# IoTaWat_DIN.net
KiCad netlist of a schematic drawn in Altium Designer
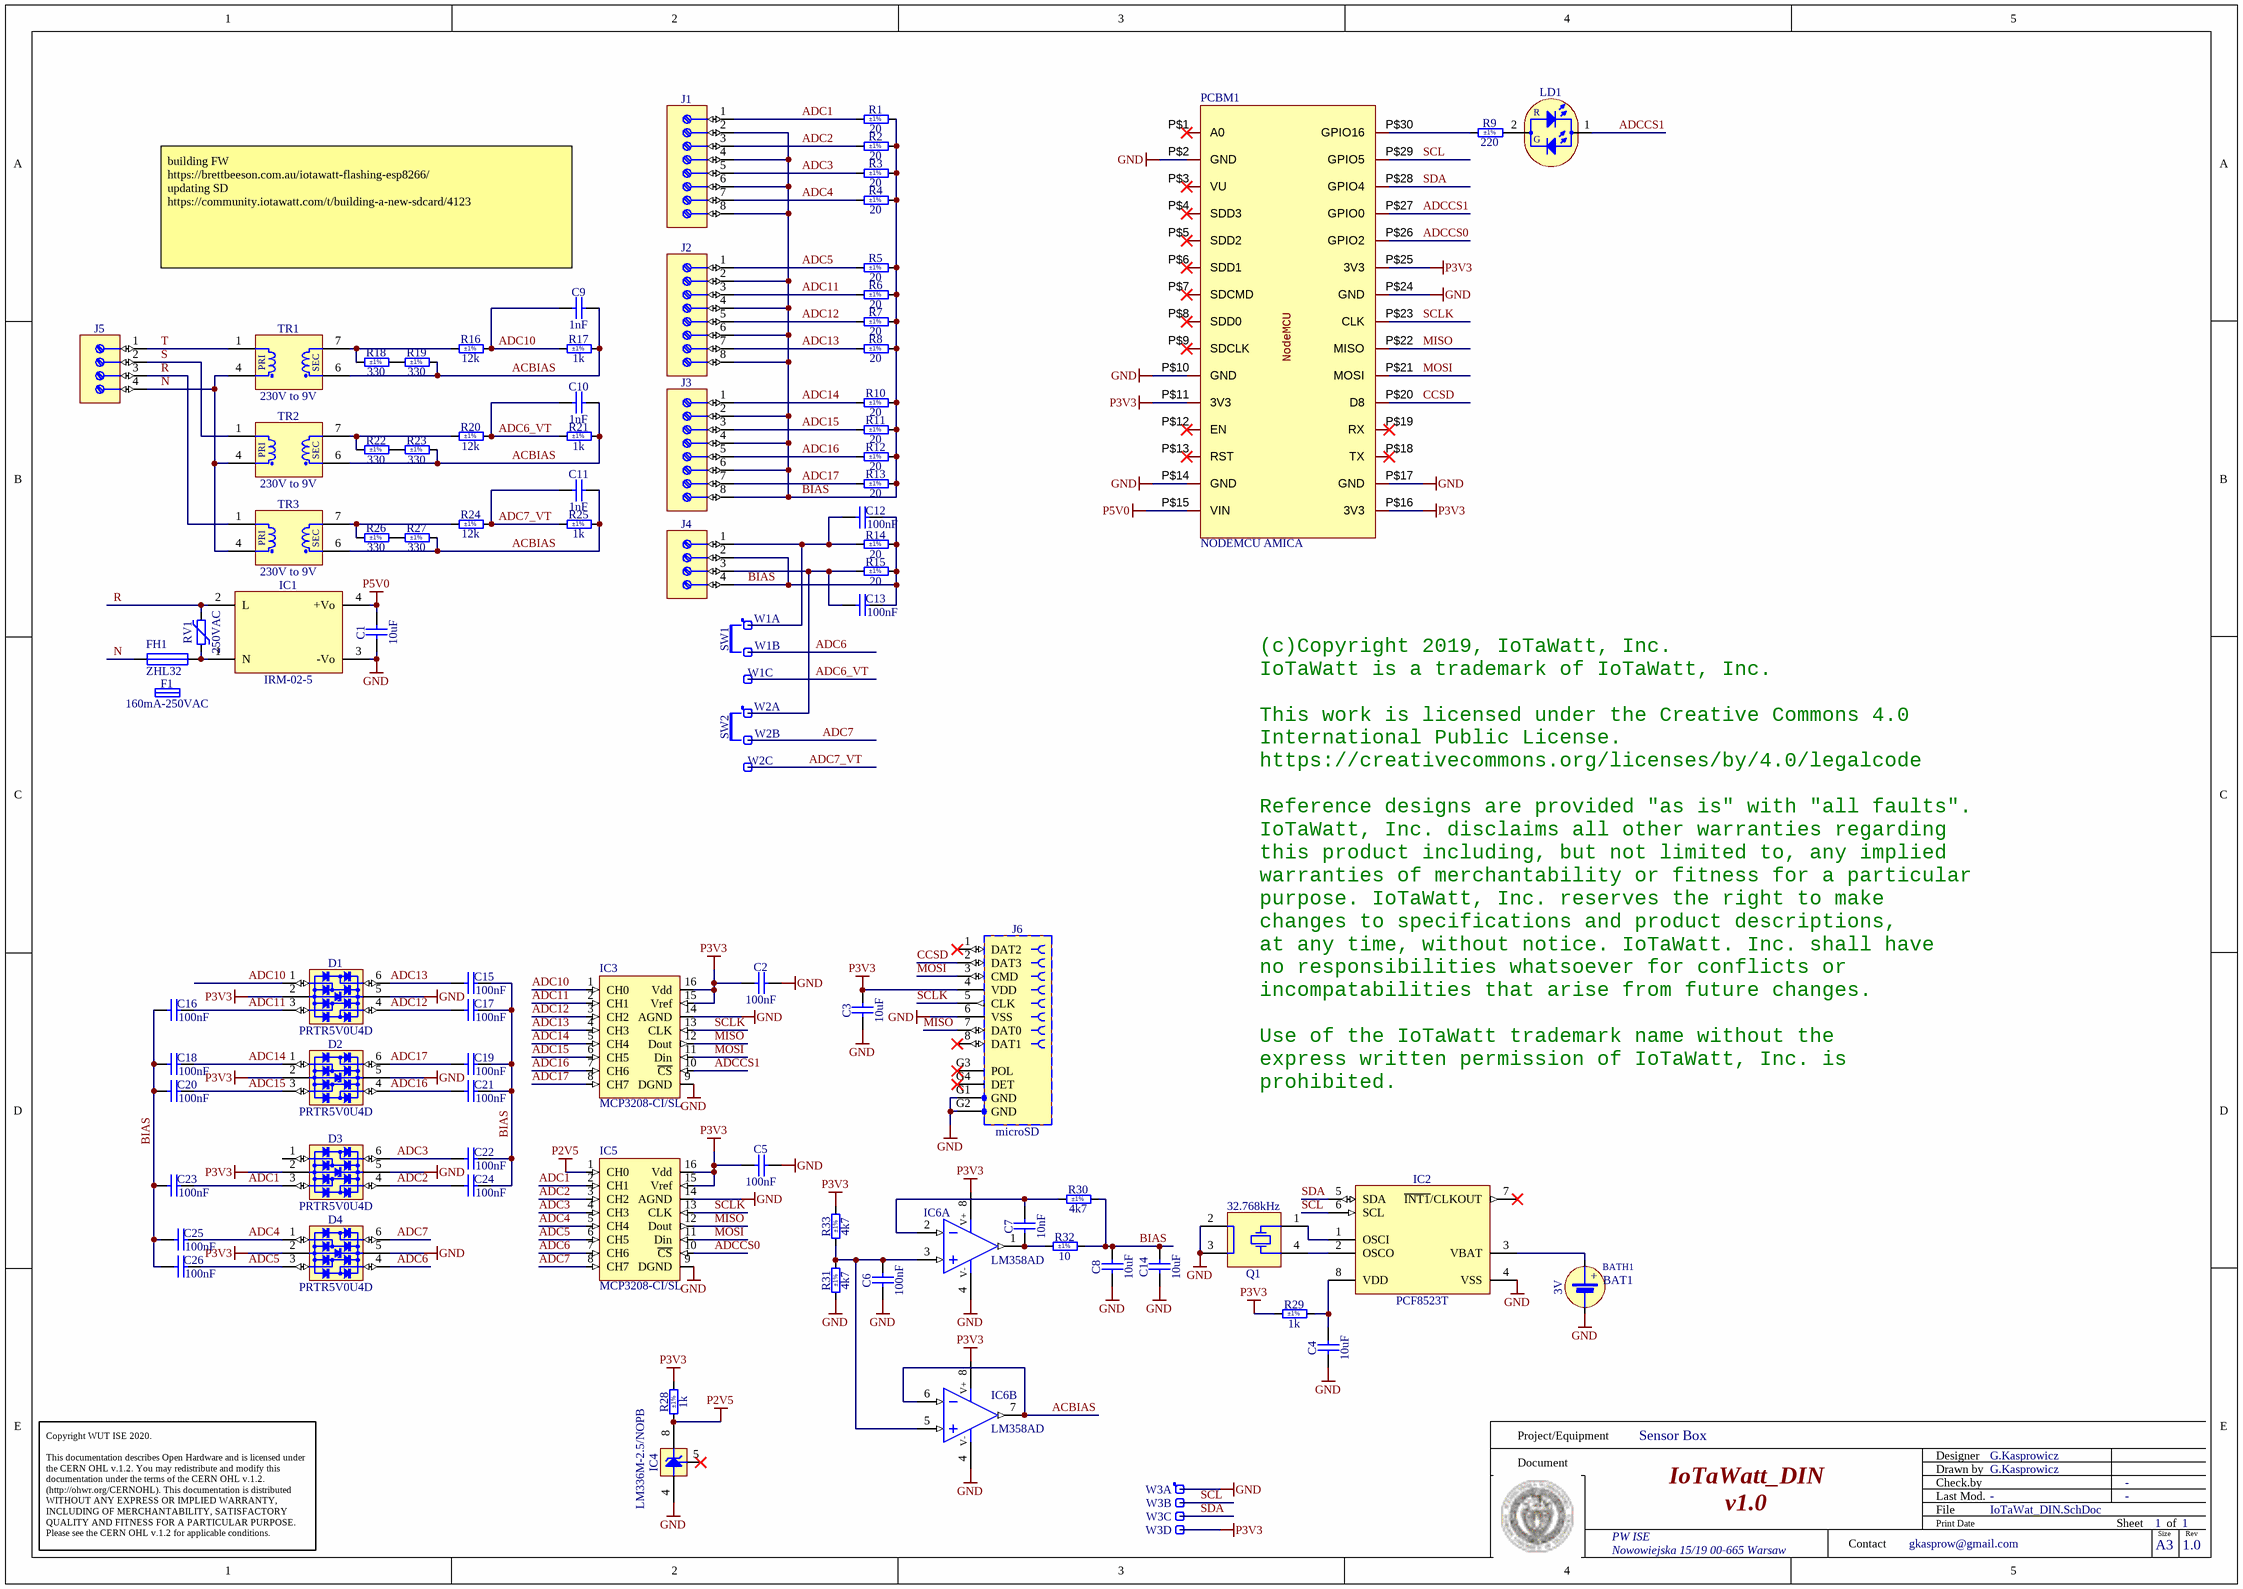
[diagram p0: IoTaWat_DIN.SchDoc]

(export (version "E")
  (design (tool "Eeschema 10.0.6"))
  (components
    (comp (ref "BAT1")
      (value "3V")
      (footprint "BAT_VARTA_CR1220")
      (description "Battery for use only with Socket Holder")
      (fields
        (field (name "PART NUMBER") "BAT_VARTA_CR1220")
        (field (name "POWER") "35mAh")
        (field (name "AUTHOR") "CERN DEM JLC")
      )
      (libsource (lib "Eletro-mechanical") (part "Battery No Pin"))
    )
    (comp (ref "BATH1")
      (value "~")
      (footprint "BATH_KEYSTONE_3000")
      (description "Battery Holder whit 2 Pin")
      (fields
        (field (name "PART NUMBER") "BATH_KEYSTONE_3000")
        (field (name "MANUFACTURER") "KEYSTONE")
        (field (name "AUTHOR") "CERN DEM JLC")
      )
      (libsource (lib "Eletro-mechanical") (part "Battery Holder 2 Pin"))
    )
    (comp (ref "C1")
      (value "10uF")
      (footprint "CAPC2012X135N")
      (description "Non-polarised capacitor")
      (fields
        (field (name "PART NUMBER") "CC0805_10UF_10V_10%_X7R")
        (field (name "VOLTAGE") "10V")
        (field (name "AUTHOR") "CERN DEM JLC")
      )
      (libsource (lib "Capacitors") (part "Capacitor - non polarized"))
    )
    (comp (ref "C2")
      (value "100nF")
      (footprint "CAPC1608X87N")
      (description "Non-polarised capacitor")
      (fields
        (field (name "PART NUMBER") "CC0603_100NF_50V_10%_X5R")
        (field (name "VOLTAGE") "50V")
        (field (name "AUTHOR") "CERN DEM MR")
      )
      (libsource (lib "Capacitors") (part "Capacitor - non polarized"))
    )
    (comp (ref "C3")
      (value "10uF")
      (footprint "CAPC2012X135N")
      (description "Non-polarised capacitor")
      (fields
        (field (name "PART NUMBER") "CC0805_10UF_10V_10%_X7R")
        (field (name "VOLTAGE") "10V")
        (field (name "AUTHOR") "CERN DEM JLC")
      )
      (libsource (lib "Capacitors") (part "Capacitor - non polarized"))
    )
    (comp (ref "C4")
      (value "10uF")
      (footprint "CAPC2012X135N")
      (description "Non-polarised capacitor")
      (fields
        (field (name "PART NUMBER") "CC0805_10UF_10V_10%_X7R")
        (field (name "VOLTAGE") "10V")
        (field (name "AUTHOR") "CERN DEM JLC")
      )
      (libsource (lib "Capacitors") (part "Capacitor - non polarized"))
    )
    (comp (ref "C5")
      (value "100nF")
      (footprint "CAPC1608X87N")
      (description "Non-polarised capacitor")
      (fields
        (field (name "PART NUMBER") "CC0603_100NF_50V_10%_X5R")
        (field (name "VOLTAGE") "50V")
        (field (name "AUTHOR") "CERN DEM MR")
      )
      (libsource (lib "Capacitors") (part "Capacitor - non polarized"))
    )
    (comp (ref "C6")
      (value "100nF")
      (footprint "CAPC1608X87N")
      (description "Non-polarised capacitor")
      (fields
        (field (name "PART NUMBER") "CC0603_100NF_50V_10%_X5R")
        (field (name "VOLTAGE") "50V")
        (field (name "AUTHOR") "CERN DEM MR")
      )
      (libsource (lib "Capacitors") (part "Capacitor - non polarized"))
    )
    (comp (ref "C7")
      (value "10nF")
      (footprint "CAPC1608X87N")
      (description "Non-polarised capacitor")
      (fields
        (field (name "PART NUMBER") "CC0603_10NF_50V_5%_C0G")
        (field (name "VOLTAGE") "50V")
        (field (name "AUTHOR") "CERN DEM JLC")
      )
      (libsource (lib "Capacitors") (part "Capacitor - non polarized"))
    )
    (comp (ref "C8")
      (value "10uF")
      (footprint "CAPC2012X135N")
      (description "Non-polarised capacitor")
      (fields
        (field (name "PART NUMBER") "CC0805_10UF_10V_10%_X7R")
        (field (name "VOLTAGE") "10V")
        (field (name "AUTHOR") "CERN DEM JLC")
      )
      (libsource (lib "Capacitors") (part "Capacitor - non polarized"))
    )
    (comp (ref "C9")
      (value "1nF")
      (footprint "CAPC1608X90N")
      (description "Non-polarised capacitor")
      (fields
        (field (name "PART NUMBER") "CC0603_1NF_50V_1%_NP0")
        (field (name "VOLTAGE") "50V")
        (field (name "AUTHOR") "CERN DEM JLC")
      )
      (libsource (lib "Capacitors") (part "Capacitor - non polarized"))
    )
    (comp (ref "C10")
      (value "1nF")
      (footprint "CAPC1608X90N")
      (description "Non-polarised capacitor")
      (fields
        (field (name "PART NUMBER") "CC0603_1NF_50V_1%_NP0")
        (field (name "VOLTAGE") "50V")
        (field (name "AUTHOR") "CERN DEM JLC")
      )
      (libsource (lib "Capacitors") (part "Capacitor - non polarized"))
    )
    (comp (ref "C11")
      (value "1nF")
      (footprint "CAPC1608X90N")
      (description "Non-polarised capacitor")
      (fields
        (field (name "PART NUMBER") "CC0603_1NF_50V_1%_NP0")
        (field (name "VOLTAGE") "50V")
        (field (name "AUTHOR") "CERN DEM JLC")
      )
      (libsource (lib "Capacitors") (part "Capacitor - non polarized"))
    )
    (comp (ref "C12")
      (value "100nF")
      (footprint "CAPC1608X87N")
      (description "Non-polarised capacitor")
      (fields
        (field (name "PART NUMBER") "CC0603_100NF_50V_10%_X5R")
        (field (name "VOLTAGE") "50V")
        (field (name "AUTHOR") "CERN DEM MR")
      )
      (libsource (lib "Capacitors") (part "Capacitor - non polarized"))
    )
    (comp (ref "C13")
      (value "100nF")
      (footprint "CAPC1608X87N")
      (description "Non-polarised capacitor")
      (fields
        (field (name "PART NUMBER") "CC0603_100NF_50V_10%_X5R")
        (field (name "VOLTAGE") "50V")
        (field (name "AUTHOR") "CERN DEM MR")
      )
      (libsource (lib "Capacitors") (part "Capacitor - non polarized"))
    )
    (comp (ref "C14")
      (value "10uF")
      (footprint "CAPC2012X135N")
      (description "Non-polarised capacitor")
      (fields
        (field (name "PART NUMBER") "CC0805_10UF_10V_10%_X7R")
        (field (name "VOLTAGE") "10V")
        (field (name "AUTHOR") "CERN DEM JLC")
      )
      (libsource (lib "Capacitors") (part "Capacitor - non polarized"))
    )
    (comp (ref "C15")
      (value "100nF")
      (footprint "CAPC1608X87N")
      (description "Non-polarised capacitor")
      (fields
        (field (name "PART NUMBER") "CC0603_100NF_50V_10%_X5R")
        (field (name "VOLTAGE") "50V")
        (field (name "AUTHOR") "CERN DEM MR")
      )
      (libsource (lib "Capacitors") (part "Capacitor - non polarized"))
    )
    (comp (ref "C16")
      (value "100nF")
      (footprint "CAPC1608X87N")
      (description "Non-polarised capacitor")
      (fields
        (field (name "PART NUMBER") "CC0603_100NF_50V_10%_X5R")
        (field (name "VOLTAGE") "50V")
        (field (name "AUTHOR") "CERN DEM MR")
      )
      (libsource (lib "Capacitors") (part "Capacitor - non polarized"))
    )
    (comp (ref "C17")
      (value "100nF")
      (footprint "CAPC1608X87N")
      (description "Non-polarised capacitor")
      (fields
        (field (name "PART NUMBER") "CC0603_100NF_50V_10%_X5R")
        (field (name "VOLTAGE") "50V")
        (field (name "AUTHOR") "CERN DEM MR")
      )
      (libsource (lib "Capacitors") (part "Capacitor - non polarized"))
    )
    (comp (ref "C18")
      (value "100nF")
      (footprint "CAPC1608X87N")
      (description "Non-polarised capacitor")
      (fields
        (field (name "PART NUMBER") "CC0603_100NF_50V_10%_X5R")
        (field (name "VOLTAGE") "50V")
        (field (name "AUTHOR") "CERN DEM MR")
      )
      (libsource (lib "Capacitors") (part "Capacitor - non polarized"))
    )
    (comp (ref "C19")
      (value "100nF")
      (footprint "CAPC1608X87N")
      (description "Non-polarised capacitor")
      (fields
        (field (name "PART NUMBER") "CC0603_100NF_50V_10%_X5R")
        (field (name "VOLTAGE") "50V")
        (field (name "AUTHOR") "CERN DEM MR")
      )
      (libsource (lib "Capacitors") (part "Capacitor - non polarized"))
    )
    (comp (ref "C20")
      (value "100nF")
      (footprint "CAPC1608X87N")
      (description "Non-polarised capacitor")
      (fields
        (field (name "PART NUMBER") "CC0603_100NF_50V_10%_X5R")
        (field (name "VOLTAGE") "50V")
        (field (name "AUTHOR") "CERN DEM MR")
      )
      (libsource (lib "Capacitors") (part "Capacitor - non polarized"))
    )
    (comp (ref "C21")
      (value "100nF")
      (footprint "CAPC1608X87N")
      (description "Non-polarised capacitor")
      (fields
        (field (name "PART NUMBER") "CC0603_100NF_50V_10%_X5R")
        (field (name "VOLTAGE") "50V")
        (field (name "AUTHOR") "CERN DEM MR")
      )
      (libsource (lib "Capacitors") (part "Capacitor - non polarized"))
    )
    (comp (ref "C22")
      (value "100nF")
      (footprint "CAPC1608X87N")
      (description "Non-polarised capacitor")
      (fields
        (field (name "PART NUMBER") "CC0603_100NF_50V_10%_X5R")
        (field (name "VOLTAGE") "50V")
        (field (name "AUTHOR") "CERN DEM MR")
      )
      (libsource (lib "Capacitors") (part "Capacitor - non polarized"))
    )
    (comp (ref "C23")
      (value "100nF")
      (footprint "CAPC1608X87N")
      (description "Non-polarised capacitor")
      (fields
        (field (name "PART NUMBER") "CC0603_100NF_50V_10%_X5R")
        (field (name "VOLTAGE") "50V")
        (field (name "AUTHOR") "CERN DEM MR")
      )
      (libsource (lib "Capacitors") (part "Capacitor - non polarized"))
    )
    (comp (ref "C24")
      (value "100nF")
      (footprint "CAPC1608X87N")
      (description "Non-polarised capacitor")
      (fields
        (field (name "PART NUMBER") "CC0603_100NF_50V_10%_X5R")
        (field (name "VOLTAGE") "50V")
        (field (name "AUTHOR") "CERN DEM MR")
      )
      (libsource (lib "Capacitors") (part "Capacitor - non polarized"))
    )
    (comp (ref "C25")
      (value "100nF")
      (footprint "CAPC1608X87N")
      (description "Non-polarised capacitor")
      (fields
        (field (name "PART NUMBER") "CC0603_100NF_50V_10%_X5R")
        (field (name "VOLTAGE") "50V")
        (field (name "AUTHOR") "CERN DEM MR")
      )
      (libsource (lib "Capacitors") (part "Capacitor - non polarized"))
    )
    (comp (ref "C26")
      (value "100nF")
      (footprint "CAPC1608X87N")
      (description "Non-polarised capacitor")
      (fields
        (field (name "PART NUMBER") "CC0603_100NF_50V_10%_X5R")
        (field (name "VOLTAGE") "50V")
        (field (name "AUTHOR") "CERN DEM MR")
      )
      (libsource (lib "Capacitors") (part "Capacitor - non polarized"))
    )
    (comp (ref "D1")
      (value "PRTR5V0U4D")
      (footprint "SOT95P275X110-6N")
      (description "Ultra Low Capacitance Quadruple Rail-to-Rail ESD Protection")
      (fields (field (name "MANUFACTURER") "NEXPERIA") (field (name "AUTHOR") "CERN DEM BC"))
      (libsource (lib "ICs And Semiconductors") (part "PRTR5V0U4D"))
    )
    (comp (ref "D2")
      (value "PRTR5V0U4D")
      (footprint "SOT95P275X110-6N")
      (description "Ultra Low Capacitance Quadruple Rail-to-Rail ESD Protection")
      (fields (field (name "MANUFACTURER") "NEXPERIA") (field (name "AUTHOR") "CERN DEM BC"))
      (libsource (lib "ICs And Semiconductors") (part "PRTR5V0U4D"))
    )
    (comp (ref "D3")
      (value "PRTR5V0U4D")
      (footprint "SOT95P275X110-6N")
      (description "Ultra Low Capacitance Quadruple Rail-to-Rail ESD Protection")
      (fields (field (name "MANUFACTURER") "NEXPERIA") (field (name "AUTHOR") "CERN DEM BC"))
      (libsource (lib "ICs And Semiconductors") (part "PRTR5V0U4D"))
    )
    (comp (ref "D4")
      (value "PRTR5V0U4D")
      (footprint "SOT95P275X110-6N")
      (description "Ultra Low Capacitance Quadruple Rail-to-Rail ESD Protection")
      (fields (field (name "MANUFACTURER") "NEXPERIA") (field (name "AUTHOR") "CERN DEM BC"))
      (libsource (lib "ICs And Semiconductors") (part "PRTR5V0U4D"))
    )
    (comp (ref "F1")
      (value "160mA-250VAC")
      (footprint "FUSE_5X20_GLASS_h")
      (description "Fuse")
      (fields
        (field (name "PART NUMBER") "FUSE_SCHURTER_0034.1508_h")
        (field (name "MANUFACTURER") "SCHURTER")
        (field (name "AUTHOR") "CERN DEM JLC")
      )
      (libsource (lib "Eletro-mechanical") (part "Fuse No Pin"))
    )
    (comp (ref "FH1")
      (value "ZHL32")
      (footprint "fuse_ZHL32")
      (description "Fuse")
      (libsource (lib "LIBRARY_SCH") (part "FUSE"))
    )
    (comp (ref "IC1")
      (value "IRM-02-5")
      (footprint "PWS_MEANWELL_IRM-02")
      (description "Power Supply")
      (fields (field (name "MANUFACTURER") "MEAN WELL") (field (name "AUTHOR") "GK"))
      (libsource (lib "Regulators_SMPS") (part "AC_DC_IRM-02-5"))
    )
    (comp (ref "IC2")
      (value "PCF8523T")
      (footprint "SOIC127P600X175-8N")
      (description "Real-Time Clock (RTC) and calendar")
      (fields (field (name "MANUFACTURER") "NXP SEMICONDUCTORS") (field (name "AUTHOR") "CERN DEM HF"))
      (libsource (lib "ICs And Semiconductors") (part "PCF8523T"))
    )
    (comp (ref "IC3")
      (value "MCP3208-CI/SL")
      (footprint "SO-16")
      (description "8-Channel 12-Bit A/D with SPI")
      (libsource (lib "ADC_DAC") (part "ADC_MCP3208"))
    )
    (comp (ref "IC4")
      (value "LM336M-2.5/NOPB")
      (footprint "SOIC127P600X175-8N")
      (description "Reference Diode")
      (fields
        (field (name "MANUFACTURER") "TEXAS INSTRUMENTS")
        (field (name "MANUFACTURER PART NUMBER") "LM336M-2.5")
        (field (name "AUTHOR") "CERN DEM JLC")
      )
      (libsource (lib "ICs And Semiconductors") (part "LM336M-2.5"))
    )
    (comp (ref "IC5")
      (value "MCP3208-CI/SL")
      (footprint "SO-16")
      (description "8-Channel 12-Bit A/D with SPI")
      (libsource (lib "ADC_DAC") (part "ADC_MCP3208"))
    )
    (comp (ref "IC6")
      (value "LM358AD")
      (footprint "SOIC127P600X175-8N")
      (description "Dual Operational Amplifier")
      (fields (field (name "MANUFACTURER") "TEXAS INSTRUMENTS") (field (name "AUTHOR") "CERN DEM JLC"))
      (libsource (lib "ICs And Semiconductors") (part "Operational Amplifier x2 Type1"))
    )
    (comp (ref "J1")
      (value "~")
      (footprint "PHOENIX_1715789")
      (description "Terminal Block, 8 Positions, Screw Connection")
      (fields
        (field (name "PART NUMBER") "PHOENIX_1715789")
        (field (name "MANUFACTURER") "PHOENIX CONTACT")
        (field (name "AUTHOR") "CERN DEM JMW")
      )
      (libsource (lib "Connectors") (part "Terminal Block_8 Positions_Screw Connection"))
    )
    (comp (ref "J2")
      (value "~")
      (footprint "PHOENIX_1715789")
      (description "Terminal Block, 8 Positions, Screw Connection")
      (fields
        (field (name "PART NUMBER") "PHOENIX_1715789")
        (field (name "MANUFACTURER") "PHOENIX CONTACT")
        (field (name "AUTHOR") "CERN DEM JMW")
      )
      (libsource (lib "Connectors") (part "Terminal Block_8 Positions_Screw Connection"))
    )
    (comp (ref "J3")
      (value "~")
      (footprint "PHOENIX_1715789")
      (description "Terminal Block, 8 Positions, Screw Connection")
      (fields
        (field (name "PART NUMBER") "PHOENIX_1715789")
        (field (name "MANUFACTURER") "PHOENIX CONTACT")
        (field (name "AUTHOR") "CERN DEM JMW")
      )
      (libsource (lib "Connectors") (part "Terminal Block_8 Positions_Screw Connection"))
    )
    (comp (ref "J4")
      (value "~")
      (footprint "PHOENIX_1715747")
      (description "Terminal Block, 4 Positions, Screw Connection")
      (fields
        (field (name "PART NUMBER") "PHOENIX_1715747")
        (field (name "MANUFACTURER") "PHOENIX CONTACT")
        (field (name "AUTHOR") "CERN DEM JMW")
      )
      (libsource (lib "Connectors") (part "Terminal Block_4 Positions_Screw Connection"))
    )
    (comp (ref "J5")
      (value "~")
      (footprint "PHOENIX_1715747")
      (description "Terminal Block, 4 Positions, Screw Connection")
      (fields
        (field (name "PART NUMBER") "PHOENIX_1715747")
        (field (name "MANUFACTURER") "PHOENIX CONTACT")
        (field (name "AUTHOR") "CERN DEM JMW")
      )
      (libsource (lib "Connectors") (part "Terminal Block_4 Positions_Screw Connection"))
    )
    (comp (ref "J6")
      (value "microSD")
      (footprint "MOLEX_47309-2651")
      (description "MicroSD Card Header with Detect Switch")
      (fields
        (field (name "PART NUMBER") "MOLEX_47309-2651")
        (field (name "MANUFACTURER") "MOLEX")
        (field (name "AUTHOR") "CERN DEM JMW")
      )
      (libsource (lib "Connectors") (part "MOLEX_47309-2651"))
    )
    (comp (ref "LD1")
      (value "Red/Green")
      (footprint "LED_KINGBRIGHT_L-937EGW")
      (description "Red/ Green Bi color LED Pin 1 = Cathode Red Anode Green")
      (fields
        (field (name "PART NUMBER") "LED_KINGBRIGHT_L-937EGW")
        (field (name "MANUFACTURER") "KINGBRIGHT")
        (field (name "AUTHOR") "CERN DEM JLC")
      )
      (libsource (lib "ICs And Semiconductors") (part "LED Red-Green 1CRAG 2ARKG"))
    )
    (comp (ref "PCBM1")
      (value "NODEMCU AMICA")
      (footprint "NODEMCU")
      (description "NodeMCU 1.0 ESP8266")
      (fields (field (name "NODEMCU") "NodeMCU"))
      (libsource (lib "Modules") (part "MOD_NODEMCU"))
    )
    (comp (ref "Q1")
      (value "32.768kHz")
      (footprint "XTAL_ABRACON_ABS25")
      (description "Crystal 4 pins 1=XTAL Control 2 And 3=NC 4=XTAL")
      (fields
        (field (name "PART NUMBER") "XTAL_32.768KHZ_ABRACON_ABS25-32.768KHZ-T")
        (field (name "MANUFACTURER") "ABRACON")
        (field (name "AUTHOR") "CERN DEM JMW")
      )
      (libsource (lib "ICs And Semiconductors") (part "Quartz Crystal 1X 2-3NC 4X"))
    )
    (comp (ref "R1")
      (value "20")
      (footprint "RESC2012X60N")
      (description "Resistor - 1%")
      (fields
        (field (name "TOLERANCE") "±1%")
        (field (name "PART NUMBER") "R0805_20R_1%_0.125W_100PPM")
        (field (name "POWER") "0.125W")
        (field (name "AUTHOR") "CERN DEM JLC")
      )
      (libsource (lib "Resistors") (part "Resistor - 1%"))
    )
    (comp (ref "R2")
      (value "20")
      (footprint "RESC2012X60N")
      (description "Resistor - 1%")
      (fields
        (field (name "TOLERANCE") "±1%")
        (field (name "PART NUMBER") "R0805_20R_1%_0.125W_100PPM")
        (field (name "POWER") "0.125W")
        (field (name "AUTHOR") "CERN DEM JLC")
      )
      (libsource (lib "Resistors") (part "Resistor - 1%"))
    )
    (comp (ref "R3")
      (value "20")
      (footprint "RESC2012X60N")
      (description "Resistor - 1%")
      (fields
        (field (name "TOLERANCE") "±1%")
        (field (name "PART NUMBER") "R0805_20R_1%_0.125W_100PPM")
        (field (name "POWER") "0.125W")
        (field (name "AUTHOR") "CERN DEM JLC")
      )
      (libsource (lib "Resistors") (part "Resistor - 1%"))
    )
    (comp (ref "R4")
      (value "20")
      (footprint "RESC2012X60N")
      (description "Resistor - 1%")
      (fields
        (field (name "TOLERANCE") "±1%")
        (field (name "PART NUMBER") "R0805_20R_1%_0.125W_100PPM")
        (field (name "POWER") "0.125W")
        (field (name "AUTHOR") "CERN DEM JLC")
      )
      (libsource (lib "Resistors") (part "Resistor - 1%"))
    )
    (comp (ref "R5")
      (value "20")
      (footprint "RESC2012X60N")
      (description "Resistor - 1%")
      (fields
        (field (name "TOLERANCE") "±1%")
        (field (name "PART NUMBER") "R0805_20R_1%_0.125W_100PPM")
        (field (name "POWER") "0.125W")
        (field (name "AUTHOR") "CERN DEM JLC")
      )
      (libsource (lib "Resistors") (part "Resistor - 1%"))
    )
    (comp (ref "R6")
      (value "20")
      (footprint "RESC2012X60N")
      (description "Resistor - 1%")
      (fields
        (field (name "TOLERANCE") "±1%")
        (field (name "PART NUMBER") "R0805_20R_1%_0.125W_100PPM")
        (field (name "POWER") "0.125W")
        (field (name "AUTHOR") "CERN DEM JLC")
      )
      (libsource (lib "Resistors") (part "Resistor - 1%"))
    )
    (comp (ref "R7")
      (value "20")
      (footprint "RESC2012X60N")
      (description "Resistor - 1%")
      (fields
        (field (name "TOLERANCE") "±1%")
        (field (name "PART NUMBER") "R0805_20R_1%_0.125W_100PPM")
        (field (name "POWER") "0.125W")
        (field (name "AUTHOR") "CERN DEM JLC")
      )
      (libsource (lib "Resistors") (part "Resistor - 1%"))
    )
    (comp (ref "R8")
      (value "20")
      (footprint "RESC2012X60N")
      (description "Resistor - 1%")
      (fields
        (field (name "TOLERANCE") "±1%")
        (field (name "PART NUMBER") "R0805_20R_1%_0.125W_100PPM")
        (field (name "POWER") "0.125W")
        (field (name "AUTHOR") "CERN DEM JLC")
      )
      (libsource (lib "Resistors") (part "Resistor - 1%"))
    )
    (comp (ref "R9")
      (value "220")
      (footprint "RESC1608X55N")
      (description "Resistor - 1%")
      (fields
        (field (name "TOLERANCE") "±1%")
        (field (name "PART NUMBER") "R0603_220R_1%_0.1W_100PPM")
        (field (name "POWER") "0.1W")
        (field (name "AUTHOR") "CERN DEM JLC")
      )
      (libsource (lib "Resistors") (part "Resistor - 1%"))
    )
    (comp (ref "R10")
      (value "20")
      (footprint "RESC2012X60N")
      (description "Resistor - 1%")
      (fields
        (field (name "TOLERANCE") "±1%")
        (field (name "PART NUMBER") "R0805_20R_1%_0.125W_100PPM")
        (field (name "POWER") "0.125W")
        (field (name "AUTHOR") "CERN DEM JLC")
      )
      (libsource (lib "Resistors") (part "Resistor - 1%"))
    )
    (comp (ref "R11")
      (value "20")
      (footprint "RESC2012X60N")
      (description "Resistor - 1%")
      (fields
        (field (name "TOLERANCE") "±1%")
        (field (name "PART NUMBER") "R0805_20R_1%_0.125W_100PPM")
        (field (name "POWER") "0.125W")
        (field (name "AUTHOR") "CERN DEM JLC")
      )
      (libsource (lib "Resistors") (part "Resistor - 1%"))
    )
    (comp (ref "R12")
      (value "20")
      (footprint "RESC2012X60N")
      (description "Resistor - 1%")
      (fields
        (field (name "TOLERANCE") "±1%")
        (field (name "PART NUMBER") "R0805_20R_1%_0.125W_100PPM")
        (field (name "POWER") "0.125W")
        (field (name "AUTHOR") "CERN DEM JLC")
      )
      (libsource (lib "Resistors") (part "Resistor - 1%"))
    )
    (comp (ref "R13")
      (value "20")
      (footprint "RESC2012X60N")
      (description "Resistor - 1%")
      (fields
        (field (name "TOLERANCE") "±1%")
        (field (name "PART NUMBER") "R0805_20R_1%_0.125W_100PPM")
        (field (name "POWER") "0.125W")
        (field (name "AUTHOR") "CERN DEM JLC")
      )
      (libsource (lib "Resistors") (part "Resistor - 1%"))
    )
    (comp (ref "R14")
      (value "20")
      (footprint "RESC2012X60N")
      (description "Resistor - 1%")
      (fields
        (field (name "TOLERANCE") "±1%")
        (field (name "PART NUMBER") "R0805_20R_1%_0.125W_100PPM")
        (field (name "POWER") "0.125W")
        (field (name "AUTHOR") "CERN DEM JLC")
      )
      (libsource (lib "Resistors") (part "Resistor - 1%"))
    )
    (comp (ref "R15")
      (value "20")
      (footprint "RESC2012X60N")
      (description "Resistor - 1%")
      (fields
        (field (name "TOLERANCE") "±1%")
        (field (name "PART NUMBER") "R0805_20R_1%_0.125W_100PPM")
        (field (name "POWER") "0.125W")
        (field (name "AUTHOR") "CERN DEM JLC")
      )
      (libsource (lib "Resistors") (part "Resistor - 1%"))
    )
    (comp (ref "R16")
      (value "12k")
      (footprint "RESC1608X55N")
      (description "Resistor - 1%")
      (fields
        (field (name "TOLERANCE") "±1%")
        (field (name "PART NUMBER") "R0603_12K_1%_0.1W_100PPM")
        (field (name "POWER") "0.1W")
        (field (name "AUTHOR") "CERN DEM JLC")
      )
      (libsource (lib "Resistors") (part "Resistor - 1%"))
    )
    (comp (ref "R17")
      (value "1k")
      (footprint "RESC1608X55N")
      (description "Resistor - 1%")
      (fields
        (field (name "TOLERANCE") "±1%")
        (field (name "PART NUMBER") "R0603_1K_1%_0.1W_100PPM")
        (field (name "POWER") "0.1W")
        (field (name "AUTHOR") "CERN DEM JLC")
      )
      (libsource (lib "Resistors") (part "Resistor - 1%"))
    )
    (comp (ref "R18")
      (value "330")
      (footprint "RESC3216X65N")
      (description "Resistor - 1%")
      (fields
        (field (name "TOLERANCE") "±1%")
        (field (name "PART NUMBER") "R1206_330R_1%_0.25W_100PPM")
        (field (name "POWER") "0.25W")
        (field (name "AUTHOR") "CERN DEM JLC")
      )
      (libsource (lib "Resistors") (part "Resistor - 1%"))
    )
    (comp (ref "R19")
      (value "330")
      (footprint "RESC3216X65N")
      (description "Resistor - 1%")
      (fields
        (field (name "TOLERANCE") "±1%")
        (field (name "PART NUMBER") "R1206_330R_1%_0.25W_100PPM")
        (field (name "POWER") "0.25W")
        (field (name "AUTHOR") "CERN DEM JLC")
      )
      (libsource (lib "Resistors") (part "Resistor - 1%"))
    )
    (comp (ref "R20")
      (value "12k")
      (footprint "RESC1608X55N")
      (description "Resistor - 1%")
      (fields
        (field (name "TOLERANCE") "±1%")
        (field (name "PART NUMBER") "R0603_12K_1%_0.1W_100PPM")
        (field (name "POWER") "0.1W")
        (field (name "AUTHOR") "CERN DEM JLC")
      )
      (libsource (lib "Resistors") (part "Resistor - 1%"))
    )
    (comp (ref "R21")
      (value "1k")
      (footprint "RESC1608X55N")
      (description "Resistor - 1%")
      (fields
        (field (name "TOLERANCE") "±1%")
        (field (name "PART NUMBER") "R0603_1K_1%_0.1W_100PPM")
        (field (name "POWER") "0.1W")
        (field (name "AUTHOR") "CERN DEM JLC")
      )
      (libsource (lib "Resistors") (part "Resistor - 1%"))
    )
    (comp (ref "R22")
      (value "330")
      (footprint "RESC3216X65N")
      (description "Resistor - 1%")
      (fields
        (field (name "TOLERANCE") "±1%")
        (field (name "PART NUMBER") "R1206_330R_1%_0.25W_100PPM")
        (field (name "POWER") "0.25W")
        (field (name "AUTHOR") "CERN DEM JLC")
      )
      (libsource (lib "Resistors") (part "Resistor - 1%"))
    )
    (comp (ref "R23")
      (value "330")
      (footprint "RESC3216X65N")
      (description "Resistor - 1%")
      (fields
        (field (name "TOLERANCE") "±1%")
        (field (name "PART NUMBER") "R1206_330R_1%_0.25W_100PPM")
        (field (name "POWER") "0.25W")
        (field (name "AUTHOR") "CERN DEM JLC")
      )
      (libsource (lib "Resistors") (part "Resistor - 1%"))
    )
    (comp (ref "R24")
      (value "12k")
      (footprint "RESC1608X55N")
      (description "Resistor - 1%")
      (fields
        (field (name "TOLERANCE") "±1%")
        (field (name "PART NUMBER") "R0603_12K_1%_0.1W_100PPM")
        (field (name "POWER") "0.1W")
        (field (name "AUTHOR") "CERN DEM JLC")
      )
      (libsource (lib "Resistors") (part "Resistor - 1%"))
    )
    (comp (ref "R25")
      (value "1k")
      (footprint "RESC1608X55N")
      (description "Resistor - 1%")
      (fields
        (field (name "TOLERANCE") "±1%")
        (field (name "PART NUMBER") "R0603_1K_1%_0.1W_100PPM")
        (field (name "POWER") "0.1W")
        (field (name "AUTHOR") "CERN DEM JLC")
      )
      (libsource (lib "Resistors") (part "Resistor - 1%"))
    )
    (comp (ref "R26")
      (value "330")
      (footprint "RESC3216X65N")
      (description "Resistor - 1%")
      (fields
        (field (name "TOLERANCE") "±1%")
        (field (name "PART NUMBER") "R1206_330R_1%_0.25W_100PPM")
        (field (name "POWER") "0.25W")
        (field (name "AUTHOR") "CERN DEM JLC")
      )
      (libsource (lib "Resistors") (part "Resistor - 1%"))
    )
    (comp (ref "R27")
      (value "330")
      (footprint "RESC3216X65N")
      (description "Resistor - 1%")
      (fields
        (field (name "TOLERANCE") "±1%")
        (field (name "PART NUMBER") "R1206_330R_1%_0.25W_100PPM")
        (field (name "POWER") "0.25W")
        (field (name "AUTHOR") "CERN DEM JLC")
      )
      (libsource (lib "Resistors") (part "Resistor - 1%"))
    )
    (comp (ref "R28")
      (value "1k")
      (footprint "RESC1608X55N")
      (description "Resistor - 1%")
      (fields
        (field (name "TOLERANCE") "±1%")
        (field (name "PART NUMBER") "R0603_1K_1%_0.1W_100PPM")
        (field (name "POWER") "0.1W")
        (field (name "AUTHOR") "CERN DEM JLC")
      )
      (libsource (lib "Resistors") (part "Resistor - 1%"))
    )
    (comp (ref "R29")
      (value "1k")
      (footprint "RESC1608X55N")
      (description "Resistor - 1%")
      (fields
        (field (name "TOLERANCE") "±1%")
        (field (name "PART NUMBER") "R0603_1K_1%_0.1W_100PPM")
        (field (name "POWER") "0.1W")
        (field (name "AUTHOR") "CERN DEM JLC")
      )
      (libsource (lib "Resistors") (part "Resistor - 1%"))
    )
    (comp (ref "R30")
      (value "4k7")
      (footprint "RESC1608X55N")
      (description "Resistor - 1%")
      (fields
        (field (name "TOLERANCE") "±1%")
        (field (name "PART NUMBER") "R0603_4K7_1%_0.1W_100PPM")
        (field (name "POWER") "0.1W")
        (field (name "AUTHOR") "CERN DEM JLC")
      )
      (libsource (lib "Resistors") (part "Resistor - 1%"))
    )
    (comp (ref "R31")
      (value "4k7")
      (footprint "RESC1608X55N")
      (description "Resistor - 1%")
      (fields
        (field (name "TOLERANCE") "±1%")
        (field (name "PART NUMBER") "R0603_4K7_1%_0.1W_100PPM")
        (field (name "POWER") "0.1W")
        (field (name "AUTHOR") "CERN DEM JLC")
      )
      (libsource (lib "Resistors") (part "Resistor - 1%"))
    )
    (comp (ref "R32")
      (value "10")
      (footprint "RESC1608X55N")
      (description "Resistor - 1%")
      (fields
        (field (name "TOLERANCE") "±1%")
        (field (name "PART NUMBER") "R0603_10R_1%_0.1W_200PPM")
        (field (name "POWER") "0.1W")
        (field (name "AUTHOR") "CERN DEM JLC")
      )
      (libsource (lib "Resistors") (part "Resistor - 1%"))
    )
    (comp (ref "R33")
      (value "4k7")
      (footprint "RESC1608X55N")
      (description "Resistor - 1%")
      (fields
        (field (name "TOLERANCE") "±1%")
        (field (name "PART NUMBER") "R0603_4K7_1%_0.1W_100PPM")
        (field (name "POWER") "0.1W")
        (field (name "AUTHOR") "CERN DEM JLC")
      )
      (libsource (lib "Resistors") (part "Resistor - 1%"))
    )
    (comp (ref "RV1")
      (value "250VAC")
      (footprint "VAR_EPCOS_B72214S0251K101")
      (description "Varistor")
      (fields
        (field (name "PART NUMBER") "VAR_EPCOS_B72214S0251K101")
        (field (name "POWER") "0.6W")
        (field (name "AUTHOR") "CERN DEM JLC")
      )
      (libsource (lib "Resistors") (part "Varistor"))
    )
    (comp (ref "SW1")
      (value "Jumper Type1")
      (footprint "JUMPER_BLACK_INSULATED_2.54MM")
      (description "Jumper 1 Pin")
      (fields
        (field (name "PART NUMBER") "COMATEL_313.1730.0.00.40.0")
        (field (name "MANUFACTURER") "KONTEK COMATEL")
        (field (name "AUTHOR") "CERN DEM JLC")
      )
      (libsource (lib "Connectors") (part "Jumper Type1"))
    )
    (comp (ref "SW2")
      (value "Jumper Type1")
      (footprint "JUMPER_BLACK_INSULATED_2.54MM")
      (description "Jumper 1 Pin")
      (fields
        (field (name "PART NUMBER") "COMATEL_313.1730.0.00.40.0")
        (field (name "MANUFACTURER") "KONTEK COMATEL")
        (field (name "AUTHOR") "CERN DEM JLC")
      )
      (libsource (lib "Connectors") (part "Jumper Type1"))
    )
    (comp (ref "TR1")
      (value "230V to 9V")
      (footprint "XFMR_BLOCK_TEZ0.5/D")
      (description "Transformer 1xPrim 1xSec Type1")
      (fields
        (field (name "PART NUMBER") "XFMR_BLOCK_TEZ0.5/D230/9V")
        (field (name "MANUFACTURER") "Breve")
        (field (name "AUTHOR") "GK")
      )
      (libsource (lib "Inductors_Transformers") (part "Tr_TEZ0.5/D230/9V"))
    )
    (comp (ref "TR2")
      (value "230V to 9V")
      (footprint "XFMR_BLOCK_TEZ0.5/D")
      (description "Transformer 1xPrim 1xSec Type1")
      (fields
        (field (name "PART NUMBER") "XFMR_BLOCK_TEZ0.5/D230/9V")
        (field (name "MANUFACTURER") "Breve")
        (field (name "AUTHOR") "GK")
      )
      (libsource (lib "Inductors_Transformers") (part "Tr_TEZ0.5/D230/9V"))
    )
    (comp (ref "TR3")
      (value "230V to 9V")
      (footprint "XFMR_BLOCK_TEZ0.5/D")
      (description "Transformer 1xPrim 1xSec Type1")
      (fields
        (field (name "PART NUMBER") "XFMR_BLOCK_TEZ0.5/D230/9V")
        (field (name "MANUFACTURER") "Breve")
        (field (name "AUTHOR") "GK")
      )
      (libsource (lib "Inductors_Transformers") (part "Tr_TEZ0.5/D230/9V"))
    )
    (comp (ref "W1")
      (value "Test Point")
      (footprint "COMATEL_385.0358.1.03.400")
      (description "3 Mini Wire-Wrap Contact Strip Header")
      (fields
        (field (name "PART NUMBER") "COMATEL_385.0358.1.03.400")
        (field (name "MANUFACTURER") "KONTEK COMATEL")
        (field (name "AUTHOR") "CERN DEM JLC")
      )
      (libsource (lib "Connectors") (part "Wire-Wrap Contact x3"))
    )
    (comp (ref "W2")
      (value "Test Point")
      (footprint "COMATEL_385.0358.1.03.400")
      (description "3 Mini Wire-Wrap Contact Strip Header")
      (fields
        (field (name "PART NUMBER") "COMATEL_385.0358.1.03.400")
        (field (name "MANUFACTURER") "KONTEK COMATEL")
        (field (name "AUTHOR") "CERN DEM JLC")
      )
      (libsource (lib "Connectors") (part "Wire-Wrap Contact x3"))
    )
    (comp (ref "W3")
      (value "Test Point")
      (footprint "COMATEL_385.0358.1.04.400")
      (description "4 Mini Wire-Wrap Contact Strip Header")
      (fields
        (field (name "PART NUMBER") "COMATEL_385.0358.1.04.400")
        (field (name "MANUFACTURER") "KONTEK COMATEL")
        (field (name "AUTHOR") "CERN DEM JLC")
      )
      (libsource (lib "Connectors") (part "Wire-Wrap Contact x4"))
    )
  )
  (nets
    (net (code "1") (name "/ACBIAS") (class "Default")
      (node (ref "C10") (pin "2") (pinfunction "2_2") (pintype "passive"))
      (node (ref "C11") (pin "2") (pinfunction "2_2") (pintype "passive"))
      (node (ref "C9") (pin "2") (pinfunction "2_2") (pintype "passive"))
      (node (ref "IC6") (pin "6") (pinfunction "IN-_6") (pintype "input"))
      (node (ref "IC6") (pin "7") (pinfunction "OUT_7") (pintype "output"))
      (node (ref "R17") (pin "2") (pinfunction "2_2") (pintype "passive"))
      (node (ref "R19") (pin "2") (pinfunction "2_2") (pintype "passive"))
      (node (ref "R21") (pin "2") (pinfunction "2_2") (pintype "passive"))
      (node (ref "R23") (pin "2") (pinfunction "2_2") (pintype "passive"))
      (node (ref "R25") (pin "2") (pinfunction "2_2") (pintype "passive"))
      (node (ref "R27") (pin "2") (pinfunction "2_2") (pintype "passive"))
      (node (ref "TR1") (pin "6") (pinfunction "6_6") (pintype "passive"))
      (node (ref "TR2") (pin "6") (pinfunction "6_6") (pintype "passive"))
      (node (ref "TR3") (pin "6") (pinfunction "6_6") (pintype "passive"))
    )
    (net (code "2") (name "/ADC1") (class "Default")
      (node (ref "C23") (pin "2") (pinfunction "2_2") (pintype "passive"))
      (node (ref "D3") (pin "3") (pinfunction "I/O2_3") (pintype "bidirectional"))
      (node (ref "IC5") (pin "2") (pinfunction "CH1_2") (pintype "input"))
      (node (ref "J1") (pin "1") (pinfunction "1_1") (pintype "bidirectional"))
      (node (ref "R1") (pin "1") (pinfunction "1_1") (pintype "passive"))
    )
    (net (code "3") (name "/ADC2") (class "Default")
      (node (ref "C24") (pin "1") (pinfunction "1_1") (pintype "passive"))
      (node (ref "D3") (pin "4") (pinfunction "I/O3_4") (pintype "bidirectional"))
      (node (ref "IC5") (pin "3") (pinfunction "CH2_3") (pintype "input"))
      (node (ref "J1") (pin "3") (pinfunction "3_3") (pintype "bidirectional"))
      (node (ref "R2") (pin "1") (pinfunction "1_1") (pintype "passive"))
    )
    (net (code "4") (name "/ADC3") (class "Default")
      (node (ref "C22") (pin "1") (pinfunction "1_1") (pintype "passive"))
      (node (ref "D3") (pin "6") (pinfunction "I/O4_6") (pintype "bidirectional"))
      (node (ref "IC5") (pin "4") (pinfunction "CH3_4") (pintype "input"))
      (node (ref "J1") (pin "5") (pinfunction "5_5") (pintype "bidirectional"))
      (node (ref "R3") (pin "1") (pinfunction "1_1") (pintype "passive"))
    )
    (net (code "5") (name "/ADC4") (class "Default")
      (node (ref "C25") (pin "2") (pinfunction "2_2") (pintype "passive"))
      (node (ref "D4") (pin "1") (pinfunction "I/O1_1") (pintype "bidirectional"))
      (node (ref "IC5") (pin "5") (pinfunction "CH4_5") (pintype "input"))
      (node (ref "J1") (pin "7") (pinfunction "7_7") (pintype "bidirectional"))
      (node (ref "R4") (pin "1") (pinfunction "1_1") (pintype "passive"))
    )
    (net (code "6") (name "/ADC5") (class "Default")
      (node (ref "C26") (pin "2") (pinfunction "2_2") (pintype "passive"))
      (node (ref "D4") (pin "3") (pinfunction "I/O2_3") (pintype "bidirectional"))
      (node (ref "IC5") (pin "6") (pinfunction "CH5_6") (pintype "input"))
      (node (ref "J2") (pin "1") (pinfunction "1_1") (pintype "bidirectional"))
      (node (ref "R5") (pin "1") (pinfunction "1_1") (pintype "passive"))
    )
    (net (code "7") (name "/ADC6") (class "Default")
      (node (ref "D4") (pin "4") (pinfunction "I/O3_4") (pintype "bidirectional"))
      (node (ref "IC5") (pin "7") (pinfunction "CH6_7") (pintype "input"))
      (node (ref "W1") (pin "2") (pinfunction "2_2") (pintype "bidirectional"))
    )
    (net (code "8") (name "/ADC6_VT") (class "Default")
      (node (ref "C10") (pin "1") (pinfunction "1_1") (pintype "passive"))
      (node (ref "R20") (pin "2") (pinfunction "2_2") (pintype "passive"))
      (node (ref "R21") (pin "1") (pinfunction "1_1") (pintype "passive"))
      (node (ref "W1") (pin "3") (pinfunction "3_3") (pintype "bidirectional"))
    )
    (net (code "9") (name "/ADC7") (class "Default")
      (node (ref "D4") (pin "6") (pinfunction "I/O4_6") (pintype "bidirectional"))
      (node (ref "IC5") (pin "8") (pinfunction "CH7_8") (pintype "input"))
      (node (ref "W2") (pin "2") (pinfunction "2_2") (pintype "bidirectional"))
    )
    (net (code "10") (name "/ADC7_VT") (class "Default")
      (node (ref "C11") (pin "1") (pinfunction "1_1") (pintype "passive"))
      (node (ref "R24") (pin "2") (pinfunction "2_2") (pintype "passive"))
      (node (ref "R25") (pin "1") (pinfunction "1_1") (pintype "passive"))
      (node (ref "W2") (pin "3") (pinfunction "3_3") (pintype "bidirectional"))
    )
    (net (code "11") (name "/ADC10") (class "Default")
      (node (ref "C9") (pin "1") (pinfunction "1_1") (pintype "passive"))
      (node (ref "D1") (pin "1") (pinfunction "I/O1_1") (pintype "bidirectional"))
      (node (ref "IC3") (pin "1") (pinfunction "CH0_1") (pintype "input"))
      (node (ref "R16") (pin "2") (pinfunction "2_2") (pintype "passive"))
      (node (ref "R17") (pin "1") (pinfunction "1_1") (pintype "passive"))
    )
    (net (code "12") (name "/ADC11") (class "Default")
      (node (ref "C16") (pin "2") (pinfunction "2_2") (pintype "passive"))
      (node (ref "D1") (pin "3") (pinfunction "I/O2_3") (pintype "bidirectional"))
      (node (ref "IC3") (pin "2") (pinfunction "CH1_2") (pintype "input"))
      (node (ref "J2") (pin "3") (pinfunction "3_3") (pintype "bidirectional"))
      (node (ref "R6") (pin "1") (pinfunction "1_1") (pintype "passive"))
    )
    (net (code "13") (name "/ADC12") (class "Default")
      (node (ref "C17") (pin "1") (pinfunction "1_1") (pintype "passive"))
      (node (ref "D1") (pin "4") (pinfunction "I/O3_4") (pintype "bidirectional"))
      (node (ref "IC3") (pin "3") (pinfunction "CH2_3") (pintype "input"))
      (node (ref "J2") (pin "5") (pinfunction "5_5") (pintype "bidirectional"))
      (node (ref "R7") (pin "1") (pinfunction "1_1") (pintype "passive"))
    )
    (net (code "14") (name "/ADC13") (class "Default")
      (node (ref "C15") (pin "1") (pinfunction "1_1") (pintype "passive"))
      (node (ref "D1") (pin "6") (pinfunction "I/O4_6") (pintype "bidirectional"))
      (node (ref "IC3") (pin "4") (pinfunction "CH3_4") (pintype "input"))
      (node (ref "J2") (pin "7") (pinfunction "7_7") (pintype "bidirectional"))
      (node (ref "R8") (pin "1") (pinfunction "1_1") (pintype "passive"))
    )
    (net (code "15") (name "/ADC14") (class "Default")
      (node (ref "C18") (pin "2") (pinfunction "2_2") (pintype "passive"))
      (node (ref "D2") (pin "1") (pinfunction "I/O1_1") (pintype "bidirectional"))
      (node (ref "IC3") (pin "5") (pinfunction "CH4_5") (pintype "input"))
      (node (ref "J3") (pin "1") (pinfunction "1_1") (pintype "bidirectional"))
      (node (ref "R10") (pin "1") (pinfunction "1_1") (pintype "passive"))
    )
    (net (code "16") (name "/ADC15") (class "Default")
      (node (ref "C20") (pin "2") (pinfunction "2_2") (pintype "passive"))
      (node (ref "D2") (pin "3") (pinfunction "I/O2_3") (pintype "bidirectional"))
      (node (ref "IC3") (pin "6") (pinfunction "CH5_6") (pintype "input"))
      (node (ref "J3") (pin "3") (pinfunction "3_3") (pintype "bidirectional"))
      (node (ref "R11") (pin "1") (pinfunction "1_1") (pintype "passive"))
    )
    (net (code "17") (name "/ADC16") (class "Default")
      (node (ref "C21") (pin "1") (pinfunction "1_1") (pintype "passive"))
      (node (ref "D2") (pin "4") (pinfunction "I/O3_4") (pintype "bidirectional"))
      (node (ref "IC3") (pin "7") (pinfunction "CH6_7") (pintype "input"))
      (node (ref "J3") (pin "5") (pinfunction "5_5") (pintype "bidirectional"))
      (node (ref "R12") (pin "1") (pinfunction "1_1") (pintype "passive"))
    )
    (net (code "18") (name "/ADC17") (class "Default")
      (node (ref "C19") (pin "1") (pinfunction "1_1") (pintype "passive"))
      (node (ref "D2") (pin "6") (pinfunction "I/O4_6") (pintype "bidirectional"))
      (node (ref "IC3") (pin "8") (pinfunction "CH7_8") (pintype "input"))
      (node (ref "J3") (pin "7") (pinfunction "7_7") (pintype "bidirectional"))
      (node (ref "R13") (pin "1") (pinfunction "1_1") (pintype "passive"))
    )
    (net (code "19") (name "/ADCCS0") (class "Default")
      (node (ref "IC5") (pin "10") (pinfunction "~{CS}_10") (pintype "input"))
      (node (ref "PCBM1") (pin "P$26") (pinfunction "GPIO2_P$26") (pintype "bidirectional"))
    )
    (net (code "20") (name "/ADCCS1") (class "Default")
      (node (ref "IC3") (pin "10") (pinfunction "~{CS}_10") (pintype "input"))
      (node (ref "LD1") (pin "1") (pinfunction "CR_1") (pintype "passive"))
      (node (ref "PCBM1") (pin "P$27") (pinfunction "GPIO0_P$27") (pintype "bidirectional"))
    )
    (net (code "21") (name "/BIAS") (class "Default")
      (node (ref "C12") (pin "2") (pinfunction "2_2") (pintype "passive"))
      (node (ref "C13") (pin "2") (pinfunction "2_2") (pintype "passive"))
      (node (ref "C14") (pin "2") (pinfunction "2_2") (pintype "passive"))
      (node (ref "C15") (pin "2") (pinfunction "2_2") (pintype "passive"))
      (node (ref "C16") (pin "1") (pinfunction "1_1") (pintype "passive"))
      (node (ref "C17") (pin "2") (pinfunction "2_2") (pintype "passive"))
      (node (ref "C18") (pin "1") (pinfunction "1_1") (pintype "passive"))
      (node (ref "C19") (pin "2") (pinfunction "2_2") (pintype "passive"))
      (node (ref "C20") (pin "1") (pinfunction "1_1") (pintype "passive"))
      (node (ref "C21") (pin "2") (pinfunction "2_2") (pintype "passive"))
      (node (ref "C22") (pin "2") (pinfunction "2_2") (pintype "passive"))
      (node (ref "C23") (pin "1") (pinfunction "1_1") (pintype "passive"))
      (node (ref "C24") (pin "2") (pinfunction "2_2") (pintype "passive"))
      (node (ref "C25") (pin "1") (pinfunction "1_1") (pintype "passive"))
      (node (ref "C26") (pin "1") (pinfunction "1_1") (pintype "passive"))
      (node (ref "C8") (pin "2") (pinfunction "2_2") (pintype "passive"))
      (node (ref "J1") (pin "2") (pinfunction "2_2") (pintype "bidirectional"))
      (node (ref "J1") (pin "4") (pinfunction "4_4") (pintype "bidirectional"))
      (node (ref "J1") (pin "6") (pinfunction "6_6") (pintype "bidirectional"))
      (node (ref "J1") (pin "8") (pinfunction "8_8") (pintype "bidirectional"))
      (node (ref "J2") (pin "2") (pinfunction "2_2") (pintype "bidirectional"))
      (node (ref "J2") (pin "4") (pinfunction "4_4") (pintype "bidirectional"))
      (node (ref "J2") (pin "6") (pinfunction "6_6") (pintype "bidirectional"))
      (node (ref "J2") (pin "8") (pinfunction "8_8") (pintype "bidirectional"))
      (node (ref "J3") (pin "2") (pinfunction "2_2") (pintype "bidirectional"))
      (node (ref "J3") (pin "4") (pinfunction "4_4") (pintype "bidirectional"))
      (node (ref "J3") (pin "6") (pinfunction "6_6") (pintype "bidirectional"))
      (node (ref "J3") (pin "8") (pinfunction "8_8") (pintype "bidirectional"))
      (node (ref "J4") (pin "2") (pinfunction "2_2") (pintype "bidirectional"))
      (node (ref "J4") (pin "4") (pinfunction "4_4") (pintype "bidirectional"))
      (node (ref "R1") (pin "2") (pinfunction "2_2") (pintype "passive"))
      (node (ref "R10") (pin "2") (pinfunction "2_2") (pintype "passive"))
      (node (ref "R11") (pin "2") (pinfunction "2_2") (pintype "passive"))
      (node (ref "R12") (pin "2") (pinfunction "2_2") (pintype "passive"))
      (node (ref "R13") (pin "2") (pinfunction "2_2") (pintype "passive"))
      (node (ref "R14") (pin "2") (pinfunction "2_2") (pintype "passive"))
      (node (ref "R15") (pin "2") (pinfunction "2_2") (pintype "passive"))
      (node (ref "R2") (pin "2") (pinfunction "2_2") (pintype "passive"))
      (node (ref "R3") (pin "2") (pinfunction "2_2") (pintype "passive"))
      (node (ref "R30") (pin "2") (pinfunction "2_2") (pintype "passive"))
      (node (ref "R32") (pin "2") (pinfunction "2_2") (pintype "passive"))
      (node (ref "R4") (pin "2") (pinfunction "2_2") (pintype "passive"))
      (node (ref "R5") (pin "2") (pinfunction "2_2") (pintype "passive"))
      (node (ref "R6") (pin "2") (pinfunction "2_2") (pintype "passive"))
      (node (ref "R7") (pin "2") (pinfunction "2_2") (pintype "passive"))
      (node (ref "R8") (pin "2") (pinfunction "2_2") (pintype "passive"))
    )
    (net (code "22") (name "/CCSD") (class "Default")
      (node (ref "J6") (pin "2") (pinfunction "DAT3_2") (pintype "bidirectional"))
      (node (ref "PCBM1") (pin "P$20") (pinfunction "D8_P$20") (pintype "bidirectional"))
    )
    (net (code "23") (name "/MISO") (class "Default")
      (node (ref "IC3") (pin "12") (pinfunction "Dout_12") (pintype "output"))
      (node (ref "IC5") (pin "12") (pinfunction "Dout_12") (pintype "output"))
      (node (ref "J6") (pin "7") (pinfunction "DAT0_7") (pintype "bidirectional"))
      (node (ref "PCBM1") (pin "P$22") (pinfunction "MISO_P$22") (pintype "bidirectional"))
    )
    (net (code "24") (name "/MOSI") (class "Default")
      (node (ref "IC3") (pin "11") (pinfunction "Din_11") (pintype "input"))
      (node (ref "IC5") (pin "11") (pinfunction "Din_11") (pintype "input"))
      (node (ref "J6") (pin "3") (pinfunction "CMD_3") (pintype "bidirectional"))
      (node (ref "PCBM1") (pin "P$21") (pinfunction "MOSI_P$21") (pintype "bidirectional"))
    )
    (net (code "25") (name "/N") (class "Default")
      (node (ref "FH1") (pin "1") (pinfunction "1_1") (pintype "passive"))
      (node (ref "J5") (pin "4") (pinfunction "4_4") (pintype "bidirectional"))
      (node (ref "TR1") (pin "4") (pinfunction "4_4") (pintype "passive"))
      (node (ref "TR2") (pin "4") (pinfunction "4_4") (pintype "passive"))
      (node (ref "TR3") (pin "4") (pinfunction "4_4") (pintype "passive"))
    )
    (net (code "26") (name "/R") (class "Default")
      (node (ref "IC1") (pin "2") (pinfunction "L_2") (pintype "power_in"))
      (node (ref "J5") (pin "3") (pinfunction "3_3") (pintype "bidirectional"))
      (node (ref "RV1") (pin "2") (pinfunction "2_2") (pintype "passive"))
      (node (ref "TR3") (pin "1") (pinfunction "1_1") (pintype "passive"))
    )
    (net (code "27") (name "/S") (class "Default")
      (node (ref "J5") (pin "2") (pinfunction "2_2") (pintype "bidirectional"))
      (node (ref "TR2") (pin "1") (pinfunction "1_1") (pintype "passive"))
    )
    (net (code "28") (name "/SCL") (class "Default")
      (node (ref "IC2") (pin "6") (pinfunction "SCL_6") (pintype "input"))
      (node (ref "PCBM1") (pin "P$29") (pinfunction "GPIO5_P$29") (pintype "bidirectional"))
      (node (ref "W3") (pin "2") (pinfunction "2_2") (pintype "bidirectional"))
    )
    (net (code "29") (name "/SCLK") (class "Default")
      (node (ref "IC3") (pin "13") (pinfunction "CLK_13") (pintype "input"))
      (node (ref "IC5") (pin "13") (pinfunction "CLK_13") (pintype "input"))
      (node (ref "J6") (pin "5") (pinfunction "CLK_5") (pintype "output"))
      (node (ref "PCBM1") (pin "P$23") (pinfunction "CLK_P$23") (pintype "bidirectional"))
    )
    (net (code "30") (name "/SDA") (class "Default")
      (node (ref "IC2") (pin "5") (pinfunction "SDA_5") (pintype "bidirectional"))
      (node (ref "PCBM1") (pin "P$28") (pinfunction "GPIO4_P$28") (pintype "bidirectional"))
      (node (ref "W3") (pin "3") (pinfunction "3_3") (pintype "bidirectional"))
    )
    (net (code "31") (name "/T") (class "Default")
      (node (ref "J5") (pin "1") (pinfunction "1_1") (pintype "bidirectional"))
      (node (ref "TR1") (pin "1") (pinfunction "1_1") (pintype "passive"))
    )
    (net (code "32") (name "GND") (class "Default")
      (node (ref "BATH1") (pin "2") (pinfunction "MINUS_2") (pintype "power_in"))
      (node (ref "C1") (pin "1") (pinfunction "1_1") (pintype "passive"))
      (node (ref "C14") (pin "1") (pinfunction "1_1") (pintype "passive"))
      (node (ref "C2") (pin "2") (pinfunction "2_2") (pintype "passive"))
      (node (ref "C3") (pin "1") (pinfunction "1_1") (pintype "passive"))
      (node (ref "C4") (pin "1") (pinfunction "1_1") (pintype "passive"))
      (node (ref "C5") (pin "2") (pinfunction "2_2") (pintype "passive"))
      (node (ref "C6") (pin "1") (pinfunction "1_1") (pintype "passive"))
      (node (ref "C8") (pin "1") (pinfunction "1_1") (pintype "passive"))
      (node (ref "D1") (pin "5") (pinfunction "VBUS_5") (pintype "power_in"))
      (node (ref "D2") (pin "5") (pinfunction "VBUS_5") (pintype "power_in"))
      (node (ref "D3") (pin "5") (pinfunction "VBUS_5") (pintype "power_in"))
      (node (ref "D4") (pin "5") (pinfunction "VBUS_5") (pintype "power_in"))
      (node (ref "IC1") (pin "3") (pinfunction "-Vo_3") (pintype "power_in"))
      (node (ref "IC2") (pin "4") (pinfunction "VSS_4") (pintype "power_in"))
      (node (ref "IC3") (pin "14") (pinfunction "AGND_14") (pintype "power_in"))
      (node (ref "IC3") (pin "9") (pinfunction "DGND_9") (pintype "power_in"))
      (node (ref "IC4") (pin "4") (pinfunction "A_4") (pintype "passive"))
      (node (ref "IC5") (pin "14") (pinfunction "AGND_14") (pintype "power_in"))
      (node (ref "IC5") (pin "9") (pinfunction "DGND_9") (pintype "power_in"))
      (node (ref "IC6") (pin "4") (pinfunction "V-_4") (pintype "power_in"))
      (node (ref "J6") (pin "6") (pinfunction "VSS_6") (pintype "power_in"))
      (node (ref "J6") (pin "G1") (pinfunction "GND_G1") (pintype "passive"))
      (node (ref "J6") (pin "G2") (pinfunction "GND_G2") (pintype "passive"))
      (node (ref "PCBM1") (pin "P$10") (pinfunction "GND_P$10") (pintype "bidirectional"))
      (node (ref "PCBM1") (pin "P$14") (pinfunction "GND_P$14") (pintype "bidirectional"))
      (node (ref "PCBM1") (pin "P$17") (pinfunction "GND_P$17") (pintype "bidirectional"))
      (node (ref "PCBM1") (pin "P$2") (pinfunction "GND_P$2") (pintype "bidirectional"))
      (node (ref "PCBM1") (pin "P$24") (pinfunction "GND_P$24") (pintype "bidirectional"))
      (node (ref "Q1") (pin "2") (pinfunction "GND_2") (pintype "power_in"))
      (node (ref "Q1") (pin "3") (pinfunction "GND_3") (pintype "power_in"))
      (node (ref "R31") (pin "1") (pinfunction "1_1") (pintype "passive"))
      (node (ref "W3") (pin "1") (pinfunction "1_1") (pintype "bidirectional"))
    )
    (net (code "33") (name "Net-(BATH1-PLUS)") (class "Default")
      (node (ref "BATH1") (pin "1") (pinfunction "PLUS_1") (pintype "power_in"))
      (node (ref "IC2") (pin "3") (pinfunction "VBAT_3") (pintype "passive"))
    )
    (net (code "34") (name "Net-(C12-Pad1)") (class "Default")
      (node (ref "C12") (pin "1") (pinfunction "1_1") (pintype "passive"))
      (node (ref "J4") (pin "1") (pinfunction "1_1") (pintype "bidirectional"))
      (node (ref "R14") (pin "1") (pinfunction "1_1") (pintype "passive"))
      (node (ref "W1") (pin "1") (pinfunction "1_1") (pintype "bidirectional"))
    )
    (net (code "35") (name "Net-(C13-Pad1)") (class "Default")
      (node (ref "C13") (pin "1") (pinfunction "1_1") (pintype "passive"))
      (node (ref "J4") (pin "3") (pinfunction "3_3") (pintype "bidirectional"))
      (node (ref "R15") (pin "1") (pinfunction "1_1") (pintype "passive"))
      (node (ref "W2") (pin "1") (pinfunction "1_1") (pintype "bidirectional"))
    )
    (net (code "36") (name "Net-(IC1-N)") (class "Default")
      (node (ref "FH1") (pin "2") (pinfunction "2_2") (pintype "passive"))
      (node (ref "IC1") (pin "1") (pinfunction "N_1") (pintype "power_in"))
      (node (ref "RV1") (pin "1") (pinfunction "1_1") (pintype "passive"))
    )
    (net (code "37") (name "Net-(IC2-OSCI)") (class "Default")
      (node (ref "IC2") (pin "1") (pinfunction "OSCI_1") (pintype "passive"))
      (node (ref "Q1") (pin "1") (pinfunction "X_1") (pintype "passive"))
    )
    (net (code "38") (name "Net-(IC2-OSCO)") (class "Default")
      (node (ref "IC2") (pin "2") (pinfunction "OSCO_2") (pintype "passive"))
      (node (ref "Q1") (pin "4") (pinfunction "X_4") (pintype "passive"))
    )
    (net (code "39") (name "Net-(IC2-VDD)") (class "Default")
      (node (ref "C4") (pin "2") (pinfunction "2_2") (pintype "passive"))
      (node (ref "IC2") (pin "8") (pinfunction "VDD_8") (pintype "power_in"))
      (node (ref "R29") (pin "2") (pinfunction "2_2") (pintype "passive"))
    )
    (net (code "40") (name "Net-(IC6A-IN+)") (class "Default")
      (node (ref "C6") (pin "2") (pinfunction "2_2") (pintype "passive"))
      (node (ref "IC6") (pin "3") (pinfunction "IN+_3") (pintype "input"))
      (node (ref "IC6") (pin "5") (pinfunction "IN+_5") (pintype "input"))
      (node (ref "R31") (pin "2") (pinfunction "2_2") (pintype "passive"))
      (node (ref "R33") (pin "1") (pinfunction "1_1") (pintype "passive"))
    )
    (net (code "41") (name "Net-(IC6A-IN-)") (class "Default")
      (node (ref "C7") (pin "2") (pinfunction "2_2") (pintype "passive"))
      (node (ref "IC6") (pin "2") (pinfunction "IN-_2") (pintype "input"))
      (node (ref "R30") (pin "1") (pinfunction "1_1") (pintype "passive"))
    )
    (net (code "42") (name "Net-(IC6A-OUT)") (class "Default")
      (node (ref "C7") (pin "1") (pinfunction "1_1") (pintype "passive"))
      (node (ref "IC6") (pin "1") (pinfunction "OUT_1") (pintype "output"))
      (node (ref "R32") (pin "1") (pinfunction "1_1") (pintype "passive"))
    )
    (net (code "43") (name "Net-(LD1-AR)") (class "Default")
      (node (ref "LD1") (pin "2") (pinfunction "AR_2") (pintype "passive"))
      (node (ref "R9") (pin "2") (pinfunction "2_2") (pintype "passive"))
    )
    (net (code "44") (name "Net-(PCBM1-GPIO16)") (class "Default")
      (node (ref "PCBM1") (pin "P$30") (pinfunction "GPIO16_P$30") (pintype "bidirectional"))
      (node (ref "R9") (pin "1") (pinfunction "1_1") (pintype "passive"))
    )
    (net (code "45") (name "Net-(R16-Pad1)") (class "Default")
      (node (ref "R16") (pin "1") (pinfunction "1_1") (pintype "passive"))
      (node (ref "R18") (pin "1") (pinfunction "1_1") (pintype "passive"))
      (node (ref "TR1") (pin "7") (pinfunction "7_7") (pintype "passive"))
    )
    (net (code "46") (name "Net-(R18-Pad2)") (class "Default")
      (node (ref "R18") (pin "2") (pinfunction "2_2") (pintype "passive"))
      (node (ref "R19") (pin "1") (pinfunction "1_1") (pintype "passive"))
    )
    (net (code "47") (name "Net-(R20-Pad1)") (class "Default")
      (node (ref "R20") (pin "1") (pinfunction "1_1") (pintype "passive"))
      (node (ref "R22") (pin "1") (pinfunction "1_1") (pintype "passive"))
      (node (ref "TR2") (pin "7") (pinfunction "7_7") (pintype "passive"))
    )
    (net (code "48") (name "Net-(R22-Pad2)") (class "Default")
      (node (ref "R22") (pin "2") (pinfunction "2_2") (pintype "passive"))
      (node (ref "R23") (pin "1") (pinfunction "1_1") (pintype "passive"))
    )
    (net (code "49") (name "Net-(R24-Pad1)") (class "Default")
      (node (ref "R24") (pin "1") (pinfunction "1_1") (pintype "passive"))
      (node (ref "R26") (pin "1") (pinfunction "1_1") (pintype "passive"))
      (node (ref "TR3") (pin "7") (pinfunction "7_7") (pintype "passive"))
    )
    (net (code "50") (name "Net-(R26-Pad2)") (class "Default")
      (node (ref "R26") (pin "2") (pinfunction "2_2") (pintype "passive"))
      (node (ref "R27") (pin "1") (pinfunction "1_1") (pintype "passive"))
    )
    (net (code "51") (name "P2V5") (class "Default")
      (node (ref "IC4") (pin "8") (pinfunction "C_8") (pintype "passive"))
      (node (ref "IC5") (pin "1") (pinfunction "CH0_1") (pintype "input"))
      (node (ref "R28") (pin "1") (pinfunction "1_1") (pintype "passive"))
    )
    (net (code "52") (name "P3V3") (class "Default")
      (node (ref "C2") (pin "1") (pinfunction "1_1") (pintype "passive"))
      (node (ref "C3") (pin "2") (pinfunction "2_2") (pintype "passive"))
      (node (ref "C5") (pin "1") (pinfunction "1_1") (pintype "passive"))
      (node (ref "D1") (pin "2") (pinfunction "GND_2") (pintype "power_in"))
      (node (ref "D2") (pin "2") (pinfunction "GND_2") (pintype "power_in"))
      (node (ref "D3") (pin "2") (pinfunction "GND_2") (pintype "power_in"))
      (node (ref "D4") (pin "2") (pinfunction "GND_2") (pintype "power_in"))
      (node (ref "IC3") (pin "15") (pinfunction "Vref_15") (pintype "input"))
      (node (ref "IC3") (pin "16") (pinfunction "Vdd_16") (pintype "power_in"))
      (node (ref "IC5") (pin "15") (pinfunction "Vref_15") (pintype "input"))
      (node (ref "IC5") (pin "16") (pinfunction "Vdd_16") (pintype "power_in"))
      (node (ref "IC6") (pin "8") (pinfunction "V+_8") (pintype "power_in"))
      (node (ref "J6") (pin "4") (pinfunction "VDD_4") (pintype "power_in"))
      (node (ref "PCBM1") (pin "P$11") (pinfunction "3V3_P$11") (pintype "bidirectional"))
      (node (ref "PCBM1") (pin "P$16") (pinfunction "3V3_P$16") (pintype "bidirectional"))
      (node (ref "PCBM1") (pin "P$25") (pinfunction "3V3_P$25") (pintype "bidirectional"))
      (node (ref "R28") (pin "2") (pinfunction "2_2") (pintype "passive"))
      (node (ref "R29") (pin "1") (pinfunction "1_1") (pintype "passive"))
      (node (ref "R33") (pin "2") (pinfunction "2_2") (pintype "passive"))
      (node (ref "W3") (pin "4") (pinfunction "4_4") (pintype "bidirectional"))
    )
    (net (code "53") (name "P5V0") (class "Default")
      (node (ref "C1") (pin "2") (pinfunction "2_2") (pintype "passive"))
      (node (ref "IC1") (pin "4") (pinfunction "+Vo_4") (pintype "power_in"))
      (node (ref "PCBM1") (pin "P$15") (pinfunction "VIN_P$15") (pintype "bidirectional"))
    )
    (net (code "54") (name "unconnected-(D3-I{slash}O1-Pad1)") (class "Default")
      (node (ref "D3") (pin "1") (pinfunction "I/O1_1") (pintype "bidirectional"))
    )
    (net (code "55") (name "unconnected-(IC2-~{INT1}{slash}CLKOUT-Pad7)") (class "Default")
      (node (ref "IC2") (pin "7") (pinfunction "~{INT1}/CLKOUT_7") (pintype "output+no_connect"))
    )
    (net (code "56") (name "unconnected-(IC4-Adj-Pad5)") (class "Default")
      (node (ref "IC4") (pin "5") (pinfunction "Adj_5") (pintype "passive+no_connect"))
    )
    (net (code "57") (name "unconnected-(J6-DAT1-Pad8)") (class "Default")
      (node (ref "J6") (pin "8") (pinfunction "DAT1_8") (pintype "bidirectional+no_connect"))
    )
    (net (code "58") (name "unconnected-(J6-DAT2-Pad1)") (class "Default")
      (node (ref "J6") (pin "1") (pinfunction "DAT2_1") (pintype "bidirectional+no_connect"))
    )
    (net (code "59") (name "unconnected-(J6-DET-PadG4)") (class "Default")
      (node (ref "J6") (pin "G4") (pinfunction "DET_G4") (pintype "passive+no_connect"))
    )
    (net (code "60") (name "unconnected-(J6-POL-PadG3)") (class "Default")
      (node (ref "J6") (pin "G3") (pinfunction "POL_G3") (pintype "passive+no_connect"))
    )
    (net (code "61") (name "unconnected-(PCBM1-A0-PadP$1)") (class "Default")
      (node (ref "PCBM1") (pin "P$1") (pinfunction "A0_P$1") (pintype "bidirectional+no_connect"))
    )
    (net (code "62") (name "unconnected-(PCBM1-EN-PadP$12)") (class "Default")
      (node (ref "PCBM1") (pin "P$12") (pinfunction "EN_P$12") (pintype "bidirectional+no_connect"))
    )
    (net (code "63") (name "unconnected-(PCBM1-RST-PadP$13)") (class "Default")
      (node (ref "PCBM1") (pin "P$13") (pinfunction "RST_P$13") (pintype "bidirectional+no_connect"))
    )
    (net (code "64") (name "unconnected-(PCBM1-RX-PadP$19)") (class "Default")
      (node (ref "PCBM1") (pin "P$19") (pinfunction "RX_P$19") (pintype "bidirectional+no_connect"))
    )
    (net (code "65") (name "unconnected-(PCBM1-SDCLK-PadP$9)") (class "Default")
      (node (ref "PCBM1") (pin "P$9") (pinfunction "SDCLK_P$9") (pintype "bidirectional+no_connect"))
    )
    (net (code "66") (name "unconnected-(PCBM1-SDCMD-PadP$7)") (class "Default")
      (node (ref "PCBM1") (pin "P$7") (pinfunction "SDCMD_P$7") (pintype "bidirectional+no_connect"))
    )
    (net (code "67") (name "unconnected-(PCBM1-SDD0-PadP$8)") (class "Default")
      (node (ref "PCBM1") (pin "P$8") (pinfunction "SDD0_P$8") (pintype "bidirectional+no_connect"))
    )
    (net (code "68") (name "unconnected-(PCBM1-SDD1-PadP$6)") (class "Default")
      (node (ref "PCBM1") (pin "P$6") (pinfunction "SDD1_P$6") (pintype "bidirectional+no_connect"))
    )
    (net (code "69") (name "unconnected-(PCBM1-SDD2-PadP$5)") (class "Default")
      (node (ref "PCBM1") (pin "P$5") (pinfunction "SDD2_P$5") (pintype "bidirectional+no_connect"))
    )
    (net (code "70") (name "unconnected-(PCBM1-SDD3-PadP$4)") (class "Default")
      (node (ref "PCBM1") (pin "P$4") (pinfunction "SDD3_P$4") (pintype "bidirectional+no_connect"))
    )
    (net (code "71") (name "unconnected-(PCBM1-TX-PadP$18)") (class "Default")
      (node (ref "PCBM1") (pin "P$18") (pinfunction "TX_P$18") (pintype "bidirectional+no_connect"))
    )
    (net (code "72") (name "unconnected-(PCBM1-VU-PadP$3)") (class "Default")
      (node (ref "PCBM1") (pin "P$3") (pinfunction "VU_P$3") (pintype "bidirectional+no_connect"))
    )
    (net (code "73") (name "unconnected-(SW1-Pad1)") (class "Default")
      (node (ref "SW1") (pin "1") (pinfunction "1_1") (pintype "bidirectional"))
    )
    (net (code "74") (name "unconnected-(SW2-Pad1)") (class "Default")
      (node (ref "SW2") (pin "1") (pinfunction "1_1") (pintype "bidirectional"))
    )
  )
)
